# ESP12E_DHT22_NO_RF_NEW_v1.net
KiCad netlist of a schematic drawn in EAGLE
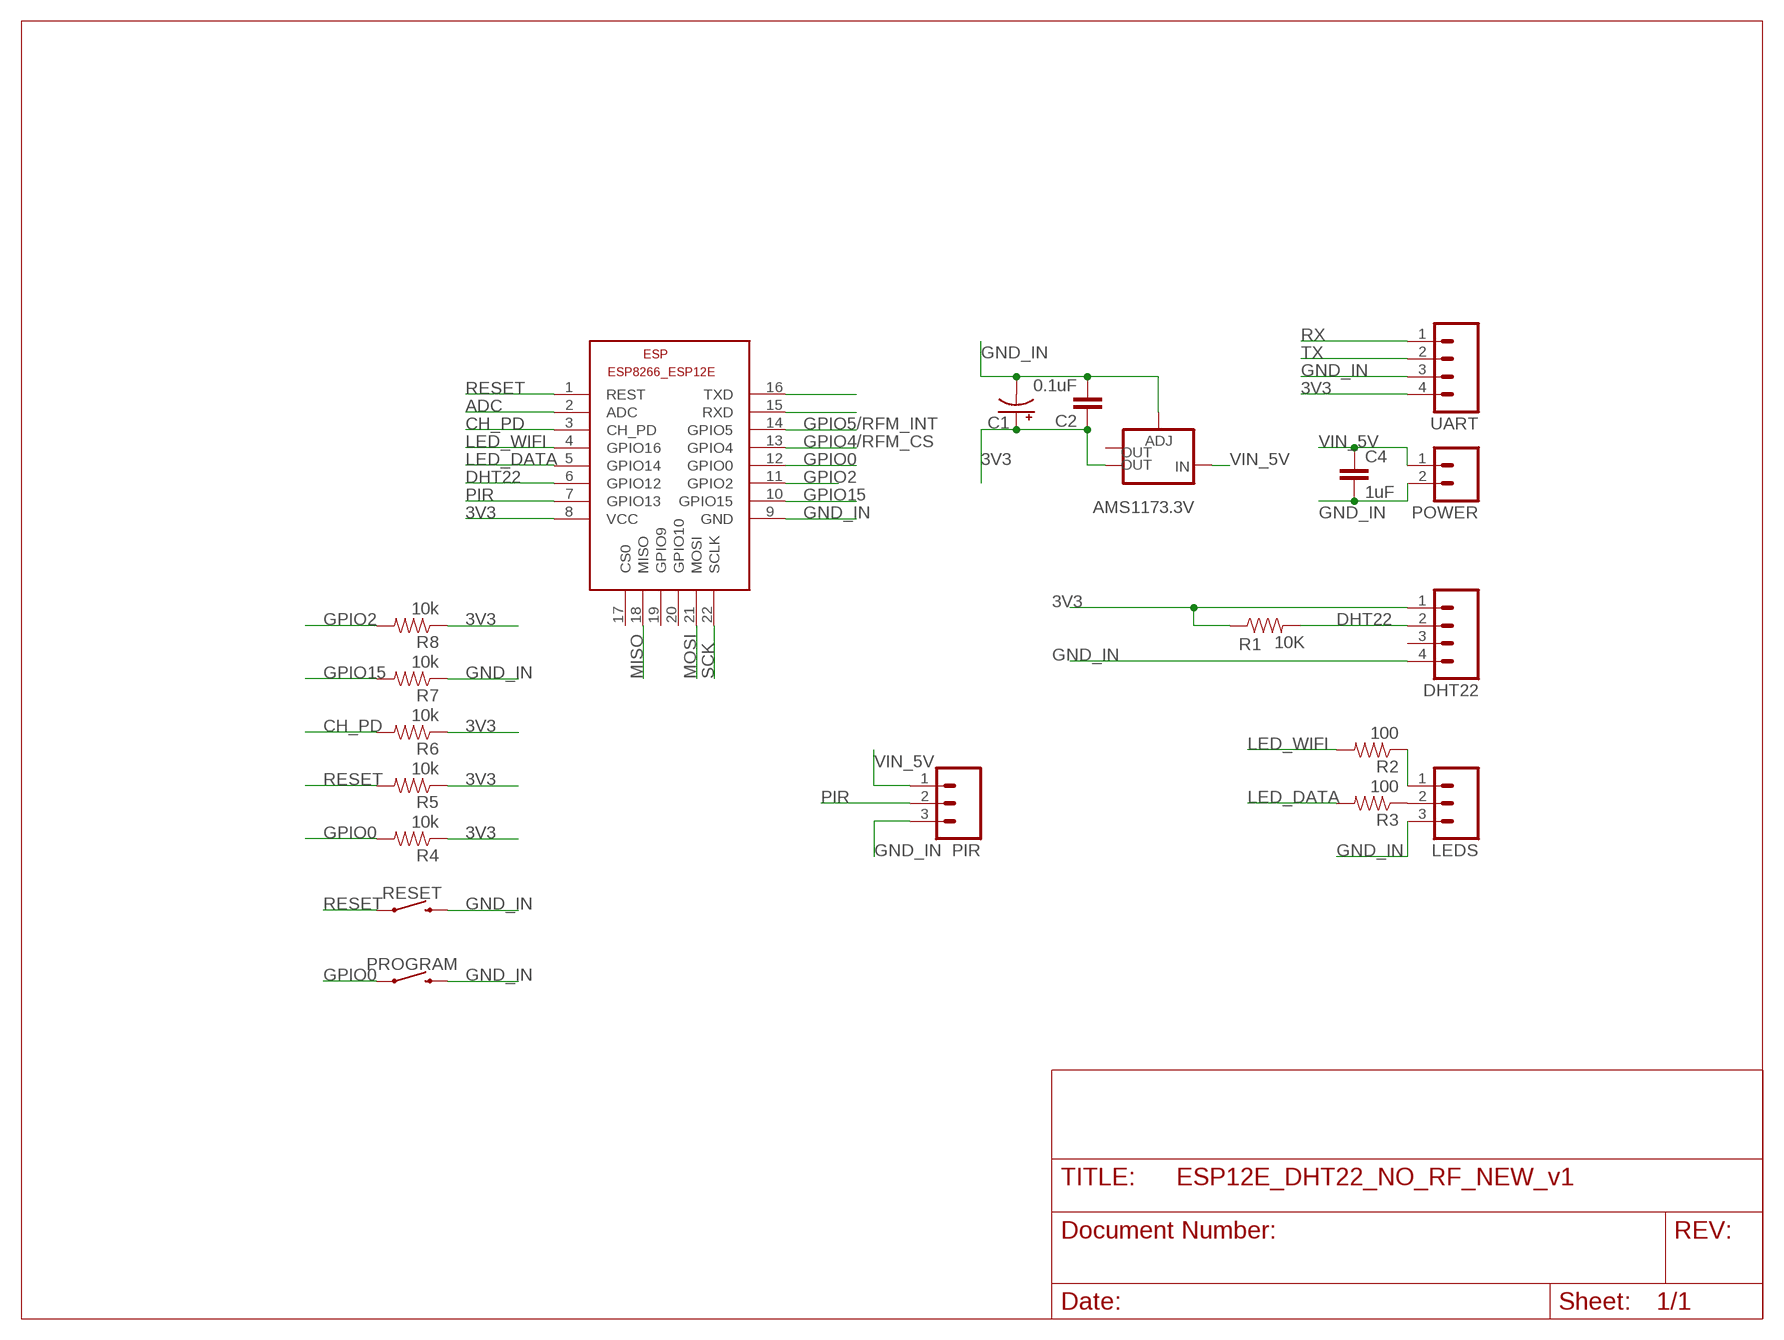
[diagram p0: schematic, sheet 1]

(export (version "E")
  (design (tool "Eeschema 10.0.6"))
  (components
    (comp (ref "AMS1173.3V")
      (value "V_REG_LM1117SOT223")
      (footprint "eagle-import:SOT223")
      (libsource (lib "eagle-import") (part "V_REG_LM1117SOT223"))
    )
    (comp (ref "C1")
      (value "CAP_POLC")
      (footprint "eagle-import:PANASONIC_C")
      (libsource (lib "eagle-import") (part "CAP_POLC"))
    )
    (comp (ref "C2")
      (value "0.1uF")
      (footprint "eagle-import:0603-CAP")
      (libsource (lib "eagle-import") (part "CAP0603-CAP"))
    )
    (comp (ref "C4")
      (value "1uF")
      (footprint "eagle-import:0603-CAP")
      (libsource (lib "eagle-import") (part "CAP0603-CAP"))
    )
    (comp (ref "DHT22")
      (value "M04LONGPADS")
      (footprint "eagle-import:1X04_LONGPADS")
      (libsource (lib "eagle-import") (part "M04LONGPADS"))
    )
    (comp (ref "ESP")
      (value "ESP8266-12EESP8266-ESP12E")
      (footprint "eagle-import:ESP8266-ESP12E")
      (libsource (lib "eagle-import") (part "ESP8266-12EESP8266-ESP12E"))
    )
    (comp (ref "LEDS")
      (value "M03PTH")
      (footprint "eagle-import:1X03")
      (libsource (lib "eagle-import") (part "M03PTH"))
    )
    (comp (ref "PIR")
      (value "M03PTH")
      (footprint "eagle-import:1X03")
      (libsource (lib "eagle-import") (part "M03PTH"))
    )
    (comp (ref "POWER")
      (value "M02PTH")
      (footprint "eagle-import:1X02")
      (libsource (lib "eagle-import") (part "M02PTH"))
    )
    (comp (ref "PROGRAM")
      (value "MOMENTARY-SWITCH-SPST-PTH-6.0MM-KIT")
      (footprint "eagle-import:TACTILE_SWITCH_PTH_6.0MM_KIT")
      (libsource (lib "eagle-import") (part "MOMENTARY-SWITCH-SPST-PTH-6.0MM-KIT"))
    )
    (comp (ref "R1")
      (value "10K")
      (footprint "eagle-import:0603-RES")
      (libsource (lib "eagle-import") (part "10KOHM-1/10W-1%(0603)0603"))
    )
    (comp (ref "R2")
      (value "100")
      (footprint "eagle-import:0603-RES")
      (libsource (lib "eagle-import") (part "RESISTOR0603"))
    )
    (comp (ref "R3")
      (value "100")
      (footprint "eagle-import:0603-RES")
      (libsource (lib "eagle-import") (part "RESISTOR0603"))
    )
    (comp (ref "R4")
      (value "10k")
      (footprint "eagle-import:0603-RES")
      (libsource (lib "eagle-import") (part "RESISTOR0603"))
    )
    (comp (ref "R5")
      (value "10k")
      (footprint "eagle-import:0603-RES")
      (libsource (lib "eagle-import") (part "RESISTOR0603"))
    )
    (comp (ref "R6")
      (value "10k")
      (footprint "eagle-import:0603-RES")
      (libsource (lib "eagle-import") (part "RESISTOR0603"))
    )
    (comp (ref "R7")
      (value "10k")
      (footprint "eagle-import:0603-RES")
      (libsource (lib "eagle-import") (part "RESISTOR0603"))
    )
    (comp (ref "R8")
      (value "10k")
      (footprint "eagle-import:0603-RES")
      (libsource (lib "eagle-import") (part "RESISTOR0603"))
    )
    (comp (ref "RESET")
      (value "MOMENTARY-SWITCH-SPST-PTH-6.0MM-KIT")
      (footprint "eagle-import:TACTILE_SWITCH_PTH_6.0MM_KIT")
      (libsource (lib "eagle-import") (part "MOMENTARY-SWITCH-SPST-PTH-6.0MM-KIT"))
    )
    (comp (ref "UART")
      (value "M04LONGPADS")
      (footprint "eagle-import:1X04_LONGPADS")
      (libsource (lib "eagle-import") (part "M04LONGPADS"))
    )
  )
  (nets
    (net (code "1") (name "/3V3") (class "Default")
      (node (ref "AMS1173.3V") (pin "2") (pinfunction "OUT_2") (pintype "output"))
      (node (ref "C1") (pin "+") (pinfunction "+_+") (pintype "passive"))
      (node (ref "C2") (pin "1") (pinfunction "1_1") (pintype "passive"))
      (node (ref "DHT22") (pin "1") (pinfunction "1_1") (pintype "passive"))
      (node (ref "ESP") (pin "8") (pinfunction "VCC_8") (pintype "bidirectional"))
      (node (ref "R1") (pin "1") (pinfunction "1_1") (pintype "passive"))
      (node (ref "R4") (pin "1") (pinfunction "1_1") (pintype "passive"))
      (node (ref "R5") (pin "1") (pinfunction "1_1") (pintype "passive"))
      (node (ref "R6") (pin "1") (pinfunction "1_1") (pintype "passive"))
      (node (ref "R8") (pin "1") (pinfunction "1_1") (pintype "passive"))
      (node (ref "UART") (pin "4") (pinfunction "4_4") (pintype "passive"))
    )
    (net (code "2") (name "/ADC") (class "Default")
      (node (ref "ESP") (pin "2") (pinfunction "ADC_2") (pintype "bidirectional"))
    )
    (net (code "3") (name "/CH_PD") (class "Default")
      (node (ref "ESP") (pin "3") (pinfunction "CH_PD_3") (pintype "bidirectional"))
      (node (ref "R6") (pin "2") (pinfunction "2_2") (pintype "passive"))
    )
    (net (code "4") (name "/DHT22") (class "Default")
      (node (ref "DHT22") (pin "2") (pinfunction "2_2") (pintype "passive"))
      (node (ref "ESP") (pin "6") (pinfunction "GPIO12_6") (pintype "bidirectional"))
      (node (ref "R1") (pin "2") (pinfunction "2_2") (pintype "passive"))
    )
    (net (code "5") (name "/GND_IN") (class "Default")
      (node (ref "AMS1173.3V") (pin "1") (pinfunction "ADJ_1") (pintype "input"))
      (node (ref "C1") (pin "-") (pinfunction "-_-") (pintype "passive"))
      (node (ref "C2") (pin "2") (pinfunction "2_2") (pintype "passive"))
      (node (ref "C4") (pin "2") (pinfunction "2_2") (pintype "passive"))
      (node (ref "DHT22") (pin "4") (pinfunction "4_4") (pintype "passive"))
      (node (ref "ESP") (pin "9") (pinfunction "GND_9") (pintype "bidirectional"))
      (node (ref "LEDS") (pin "3") (pinfunction "3_3") (pintype "passive"))
      (node (ref "PIR") (pin "3") (pinfunction "3_3") (pintype "passive"))
      (node (ref "POWER") (pin "2") (pinfunction "2_2") (pintype "passive"))
      (node (ref "PROGRAM") (pin "3") (pinfunction "2_3") (pintype "passive"))
      (node (ref "R7") (pin "1") (pinfunction "1_1") (pintype "passive"))
      (node (ref "RESET") (pin "3") (pinfunction "2_3") (pintype "passive"))
      (node (ref "UART") (pin "3") (pinfunction "3_3") (pintype "passive"))
    )
    (net (code "6") (name "/GPIO0") (class "Default")
      (node (ref "ESP") (pin "12") (pinfunction "GPIO0_12") (pintype "bidirectional"))
      (node (ref "PROGRAM") (pin "1") (pinfunction "1_1") (pintype "passive"))
      (node (ref "R4") (pin "2") (pinfunction "2_2") (pintype "passive"))
    )
    (net (code "7") (name "/GPIO2") (class "Default")
      (node (ref "ESP") (pin "11") (pinfunction "GPIO2_11") (pintype "bidirectional"))
      (node (ref "R8") (pin "2") (pinfunction "2_2") (pintype "passive"))
    )
    (net (code "8") (name "/GPIO4{slash}RFM_CS") (class "Default")
      (node (ref "ESP") (pin "13") (pinfunction "GPIO4_13") (pintype "bidirectional"))
    )
    (net (code "9") (name "/GPIO5{slash}RFM_INT") (class "Default")
      (node (ref "ESP") (pin "14") (pinfunction "GPIO5_14") (pintype "bidirectional"))
    )
    (net (code "10") (name "/GPIO15") (class "Default")
      (node (ref "ESP") (pin "10") (pinfunction "GPIO15_10") (pintype "bidirectional"))
      (node (ref "R7") (pin "2") (pinfunction "2_2") (pintype "passive"))
    )
    (net (code "11") (name "/LED_DATA") (class "Default")
      (node (ref "ESP") (pin "5") (pinfunction "GPIO14_5") (pintype "bidirectional"))
      (node (ref "R3") (pin "2") (pinfunction "2_2") (pintype "passive"))
    )
    (net (code "12") (name "/LED_WIFI") (class "Default")
      (node (ref "ESP") (pin "4") (pinfunction "GPIO16_4") (pintype "bidirectional"))
      (node (ref "R2") (pin "2") (pinfunction "2_2") (pintype "passive"))
    )
    (net (code "13") (name "/MISO") (class "Default")
      (node (ref "ESP") (pin "18") (pinfunction "MISO_18") (pintype "bidirectional"))
    )
    (net (code "14") (name "/MOSI") (class "Default")
      (node (ref "ESP") (pin "21") (pinfunction "MOSI_21") (pintype "bidirectional"))
    )
    (net (code "15") (name "/PIR") (class "Default")
      (node (ref "ESP") (pin "7") (pinfunction "GPIO13_7") (pintype "bidirectional"))
      (node (ref "PIR") (pin "2") (pinfunction "2_2") (pintype "passive"))
    )
    (net (code "16") (name "/RESET") (class "Default")
      (node (ref "ESP") (pin "1") (pinfunction "REST_1") (pintype "bidirectional"))
      (node (ref "R5") (pin "2") (pinfunction "2_2") (pintype "passive"))
      (node (ref "RESET") (pin "1") (pinfunction "1_1") (pintype "passive"))
    )
    (net (code "17") (name "/RX") (class "Default")
      (node (ref "ESP") (pin "16") (pinfunction "TXD_16") (pintype "bidirectional"))
      (node (ref "UART") (pin "1") (pinfunction "1_1") (pintype "passive"))
    )
    (net (code "18") (name "/SCK") (class "Default")
      (node (ref "ESP") (pin "22") (pinfunction "SCLK_22") (pintype "bidirectional"))
    )
    (net (code "19") (name "/TX") (class "Default")
      (node (ref "ESP") (pin "15") (pinfunction "RXD_15") (pintype "bidirectional"))
      (node (ref "UART") (pin "2") (pinfunction "2_2") (pintype "passive"))
    )
    (net (code "20") (name "/VIN_5V") (class "Default")
      (node (ref "AMS1173.3V") (pin "3") (pinfunction "IN_3") (pintype "input"))
      (node (ref "C4") (pin "1") (pinfunction "1_1") (pintype "passive"))
      (node (ref "PIR") (pin "1") (pinfunction "1_1") (pintype "passive"))
      (node (ref "POWER") (pin "1") (pinfunction "1_1") (pintype "passive"))
    )
    (net (code "21") (name "Net-(LEDS-Pad1)") (class "Default")
      (node (ref "LEDS") (pin "1") (pinfunction "1_1") (pintype "passive"))
      (node (ref "R2") (pin "1") (pinfunction "1_1") (pintype "passive"))
    )
    (net (code "22") (name "Net-(LEDS-Pad2)") (class "Default")
      (node (ref "LEDS") (pin "2") (pinfunction "2_2") (pintype "passive"))
      (node (ref "R3") (pin "1") (pinfunction "1_1") (pintype "passive"))
    )
    (net (code "23") (name "unconnected-(AMS1173.3V-OUT-Pad4)") (class "Default")
      (node (ref "AMS1173.3V") (pin "4") (pinfunction "OUT_4") (pintype "output"))
    )
    (net (code "24") (name "unconnected-(DHT22-Pad3)") (class "Default")
      (node (ref "DHT22") (pin "3") (pinfunction "3_3") (pintype "passive"))
    )
    (net (code "25") (name "unconnected-(ESP-CS0-Pad17)") (class "Default")
      (node (ref "ESP") (pin "17") (pinfunction "CS0_17") (pintype "bidirectional"))
    )
    (net (code "26") (name "unconnected-(ESP-GPIO9-Pad19)") (class "Default")
      (node (ref "ESP") (pin "19") (pinfunction "GPIO9_19") (pintype "bidirectional"))
    )
    (net (code "27") (name "unconnected-(ESP-GPIO10-Pad20)") (class "Default")
      (node (ref "ESP") (pin "20") (pinfunction "GPIO10_20") (pintype "bidirectional"))
    )
  )
)
